# roomba_wall_v2_e.net
KiCad netlist of a schematic drawn in EAGLE
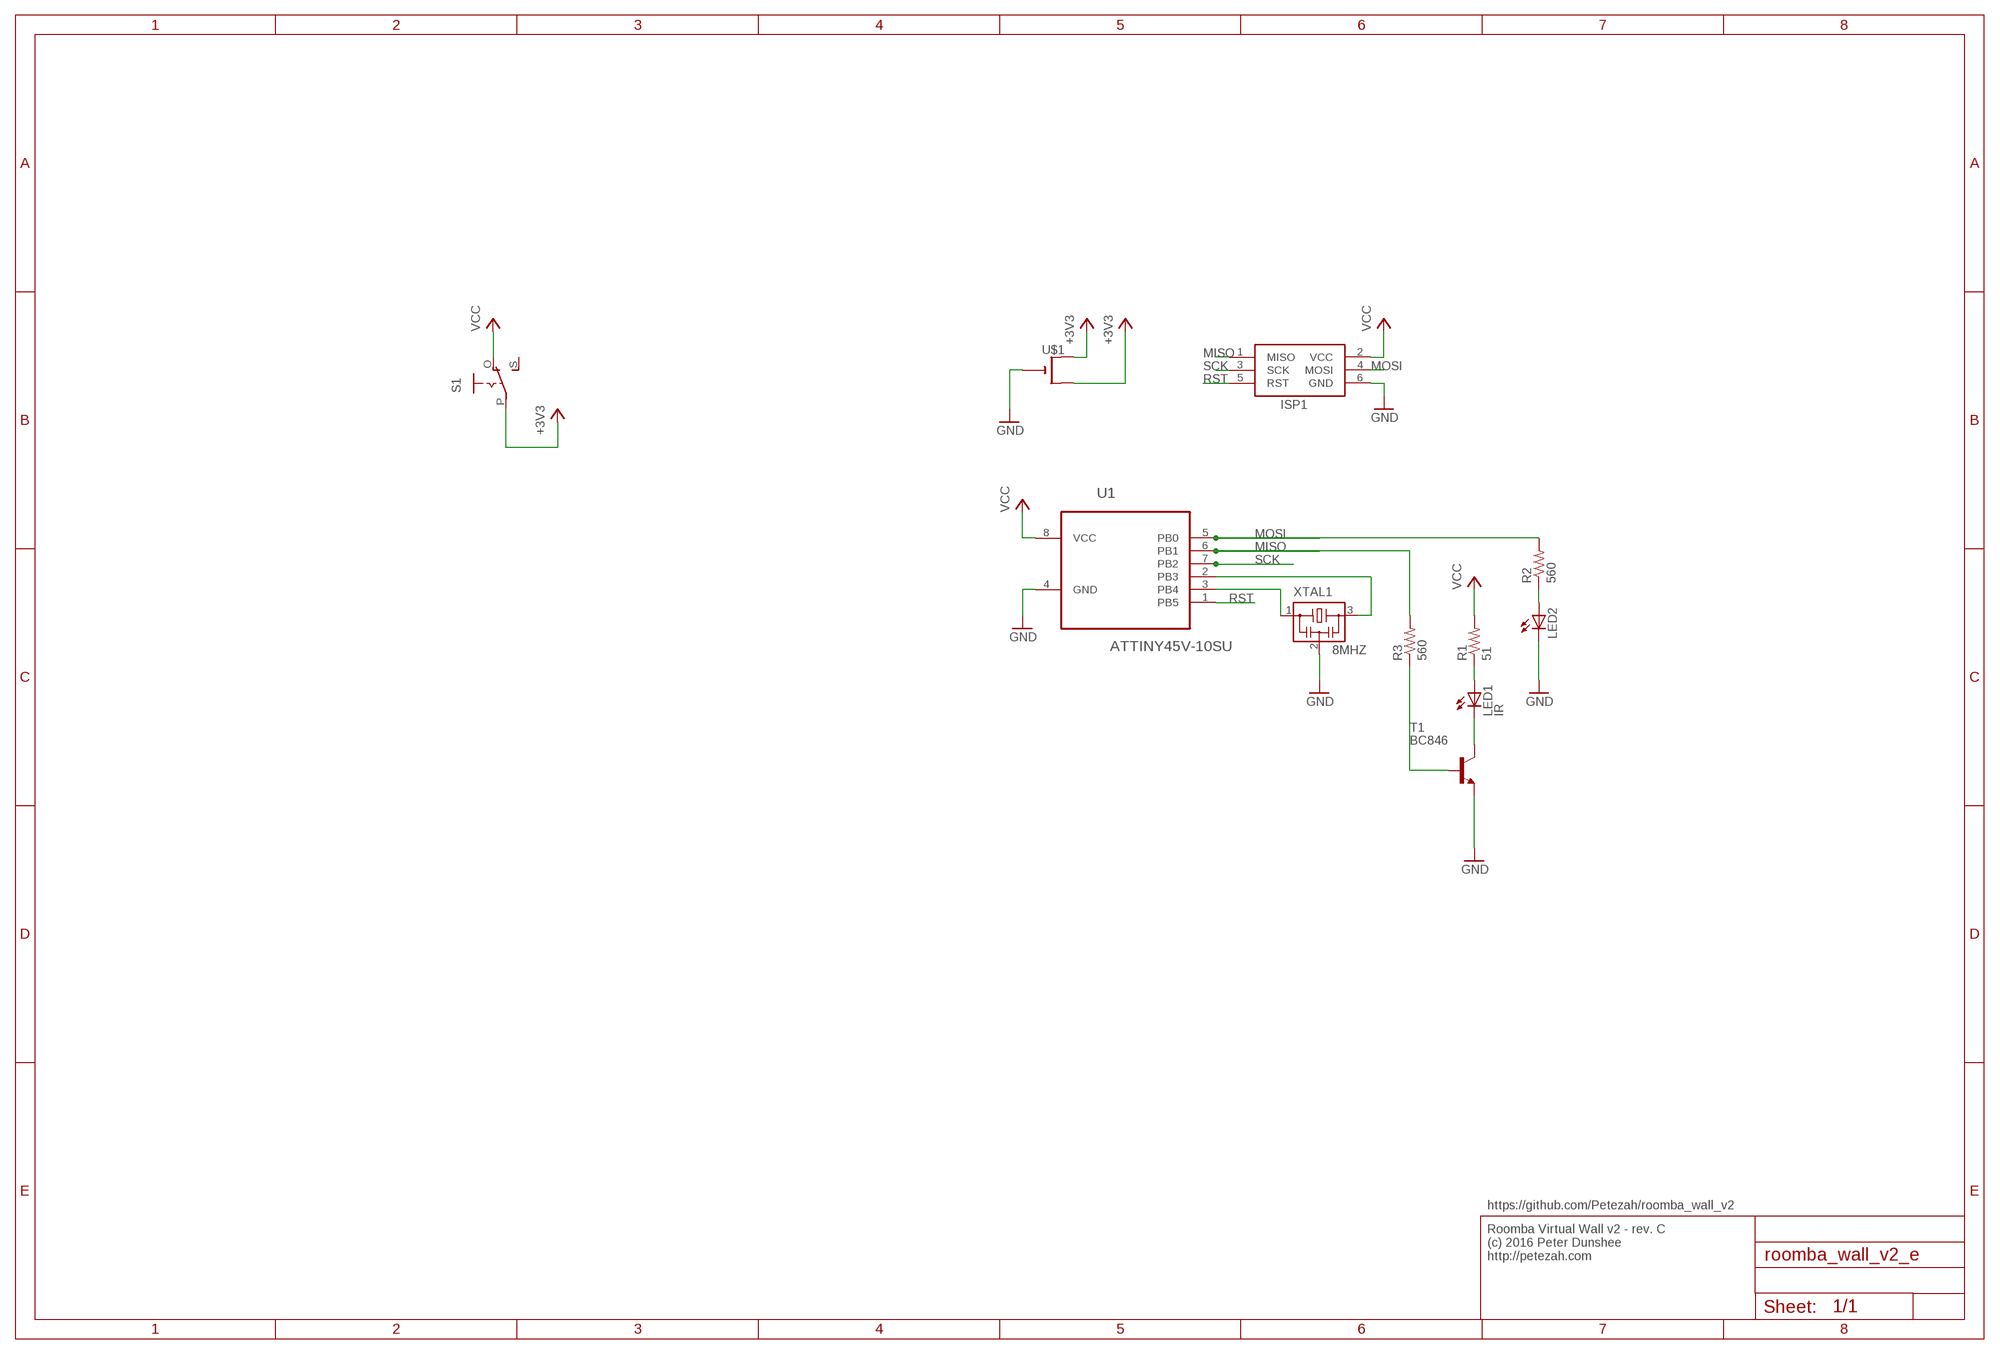
[diagram p0: schematic, sheet 1]

(export (version "E")
  (design (tool "Eeschema 10.0.6"))
  (components
    (comp (ref "ISP1")
      (value "AVRISP-6")
      (footprint "eagle-import:AVRISP")
      (libsource (lib "eagle-import") (part "AVRISP-6"))
    )
    (comp (ref "LED1")
      (value "IR")
      (footprint "eagle-import:CHIPLED_0603")
      (libsource (lib "eagle-import") (part "LEDCHIPLED_0603"))
    )
    (comp (ref "LED2")
      (value "LEDCHIPLED_1206")
      (footprint "eagle-import:CHIPLED_1206")
      (libsource (lib "eagle-import") (part "LEDCHIPLED_1206"))
    )
    (comp (ref "R1")
      (value "51")
      (footprint "eagle-import:R1206")
      (libsource (lib "eagle-import") (part "R-US_R1206"))
    )
    (comp (ref "R2")
      (value "560")
      (footprint "eagle-import:R1206")
      (libsource (lib "eagle-import") (part "R-US_R1206"))
    )
    (comp (ref "R3")
      (value "560")
      (footprint "eagle-import:R1206")
      (libsource (lib "eagle-import") (part "R-US_R1206"))
    )
    (comp (ref "S1")
      (value "EG1218S")
      (footprint "eagle-import:EG1218")
      (libsource (lib "eagle-import") (part "EG1218S"))
    )
    (comp (ref "T1")
      (value "BC846")
      (footprint "eagle-import:SOT23")
      (libsource (lib "eagle-import") (part "BC846"))
    )
    (comp (ref "U$1")
      (value "CR2032THM")
      (footprint "eagle-import:CR2032-THRU")
      (libsource (lib "eagle-import") (part "CR2032THM"))
    )
    (comp (ref "U1")
      (value "ATTINY45V-10SU")
      (footprint "eagle-import:SOIC127P798X216-8N")
      (libsource (lib "eagle-import") (part "ATTINY45V-10SU"))
    )
    (comp (ref "XTAL1")
      (value "8MHZ")
      (footprint "eagle-import:CSTCR6M")
      (fields (field (name "MPN") "CSTCR6M00G53-R0"))
      (libsource (lib "eagle-import") (part "CSTCR6M00G53Z"))
    )
  )
  (nets
    (net (code "1") (name "+3V3") (class "Default")
      (node (ref "S1") (pin "P") (pinfunction "P_P") (pintype "passive"))
      (node (ref "U$1") (pin "+1") (pinfunction "+_+1") (pintype "passive"))
      (node (ref "U$1") (pin "+2") (pinfunction "+1_+2") (pintype "passive"))
    )
    (net (code "2") (name "/MISO") (class "Default")
      (node (ref "ISP1") (pin "1") (pinfunction "MISO_1") (pintype "input"))
      (node (ref "R3") (pin "2") (pinfunction "2_2") (pintype "passive"))
      (node (ref "U1") (pin "6") (pinfunction "PB1_6") (pintype "bidirectional"))
    )
    (net (code "3") (name "/MOSI") (class "Default")
      (node (ref "ISP1") (pin "4") (pinfunction "MOSI_4") (pintype "output"))
      (node (ref "R2") (pin "2") (pinfunction "2_2") (pintype "passive"))
      (node (ref "U1") (pin "5") (pinfunction "PB0_5") (pintype "bidirectional"))
    )
    (net (code "4") (name "/RST") (class "Default")
      (node (ref "ISP1") (pin "5") (pinfunction "RST_5") (pintype "output"))
      (node (ref "U1") (pin "1") (pinfunction "PB5_1") (pintype "bidirectional"))
    )
    (net (code "5") (name "/SCK") (class "Default")
      (node (ref "ISP1") (pin "3") (pinfunction "SCK_3") (pintype "output"))
      (node (ref "U1") (pin "7") (pinfunction "PB2_7") (pintype "bidirectional"))
    )
    (net (code "6") (name "GND") (class "Default")
      (node (ref "ISP1") (pin "6") (pinfunction "GND_6") (pintype "power_in"))
      (node (ref "LED2") (pin "C") (pinfunction "C_C") (pintype "passive"))
      (node (ref "T1") (pin "2") (pinfunction "E_2") (pintype "passive"))
      (node (ref "U$1") (pin "-") (pinfunction "-_-") (pintype "passive"))
      (node (ref "U1") (pin "4") (pinfunction "GND_4") (pintype "passive"))
      (node (ref "XTAL1") (pin "2") (pinfunction "2_2") (pintype "passive"))
    )
    (net (code "7") (name "Net-(LED1-PadA)") (class "Default")
      (node (ref "LED1") (pin "A") (pinfunction "A_A") (pintype "passive"))
      (node (ref "R1") (pin "1") (pinfunction "1_1") (pintype "passive"))
    )
    (net (code "8") (name "Net-(LED2-PadA)") (class "Default")
      (node (ref "LED2") (pin "A") (pinfunction "A_A") (pintype "passive"))
      (node (ref "R2") (pin "1") (pinfunction "1_1") (pintype "passive"))
    )
    (net (code "9") (name "Net-(T1-B)") (class "Default")
      (node (ref "R3") (pin "1") (pinfunction "1_1") (pintype "passive"))
      (node (ref "T1") (pin "1") (pinfunction "B_1") (pintype "passive"))
    )
    (net (code "10") (name "Net-(T1-C)") (class "Default")
      (node (ref "LED1") (pin "C") (pinfunction "C_C") (pintype "passive"))
      (node (ref "T1") (pin "3") (pinfunction "C_3") (pintype "passive"))
    )
    (net (code "11") (name "Net-(U1-PB3)") (class "Default")
      (node (ref "U1") (pin "2") (pinfunction "PB3_2") (pintype "bidirectional"))
      (node (ref "XTAL1") (pin "3") (pinfunction "3_3") (pintype "passive"))
    )
    (net (code "12") (name "Net-(U1-PB4)") (class "Default")
      (node (ref "U1") (pin "3") (pinfunction "PB4_3") (pintype "bidirectional"))
      (node (ref "XTAL1") (pin "1") (pinfunction "1_1") (pintype "passive"))
    )
    (net (code "13") (name "VCC") (class "Default")
      (node (ref "ISP1") (pin "2") (pinfunction "VCC_2") (pintype "power_in"))
      (node (ref "R1") (pin "2") (pinfunction "2_2") (pintype "passive"))
      (node (ref "S1") (pin "O") (pinfunction "O_O") (pintype "passive"))
      (node (ref "U1") (pin "8") (pinfunction "VCC_8") (pintype "power_in"))
    )
    (net (code "14") (name "unconnected-(S1-PadS)") (class "Default")
      (node (ref "S1") (pin "S") (pinfunction "S_S") (pintype "passive"))
    )
  )
)
